# rc64kram62256ram.net
KiCad netlist of a schematic drawn in EAGLE
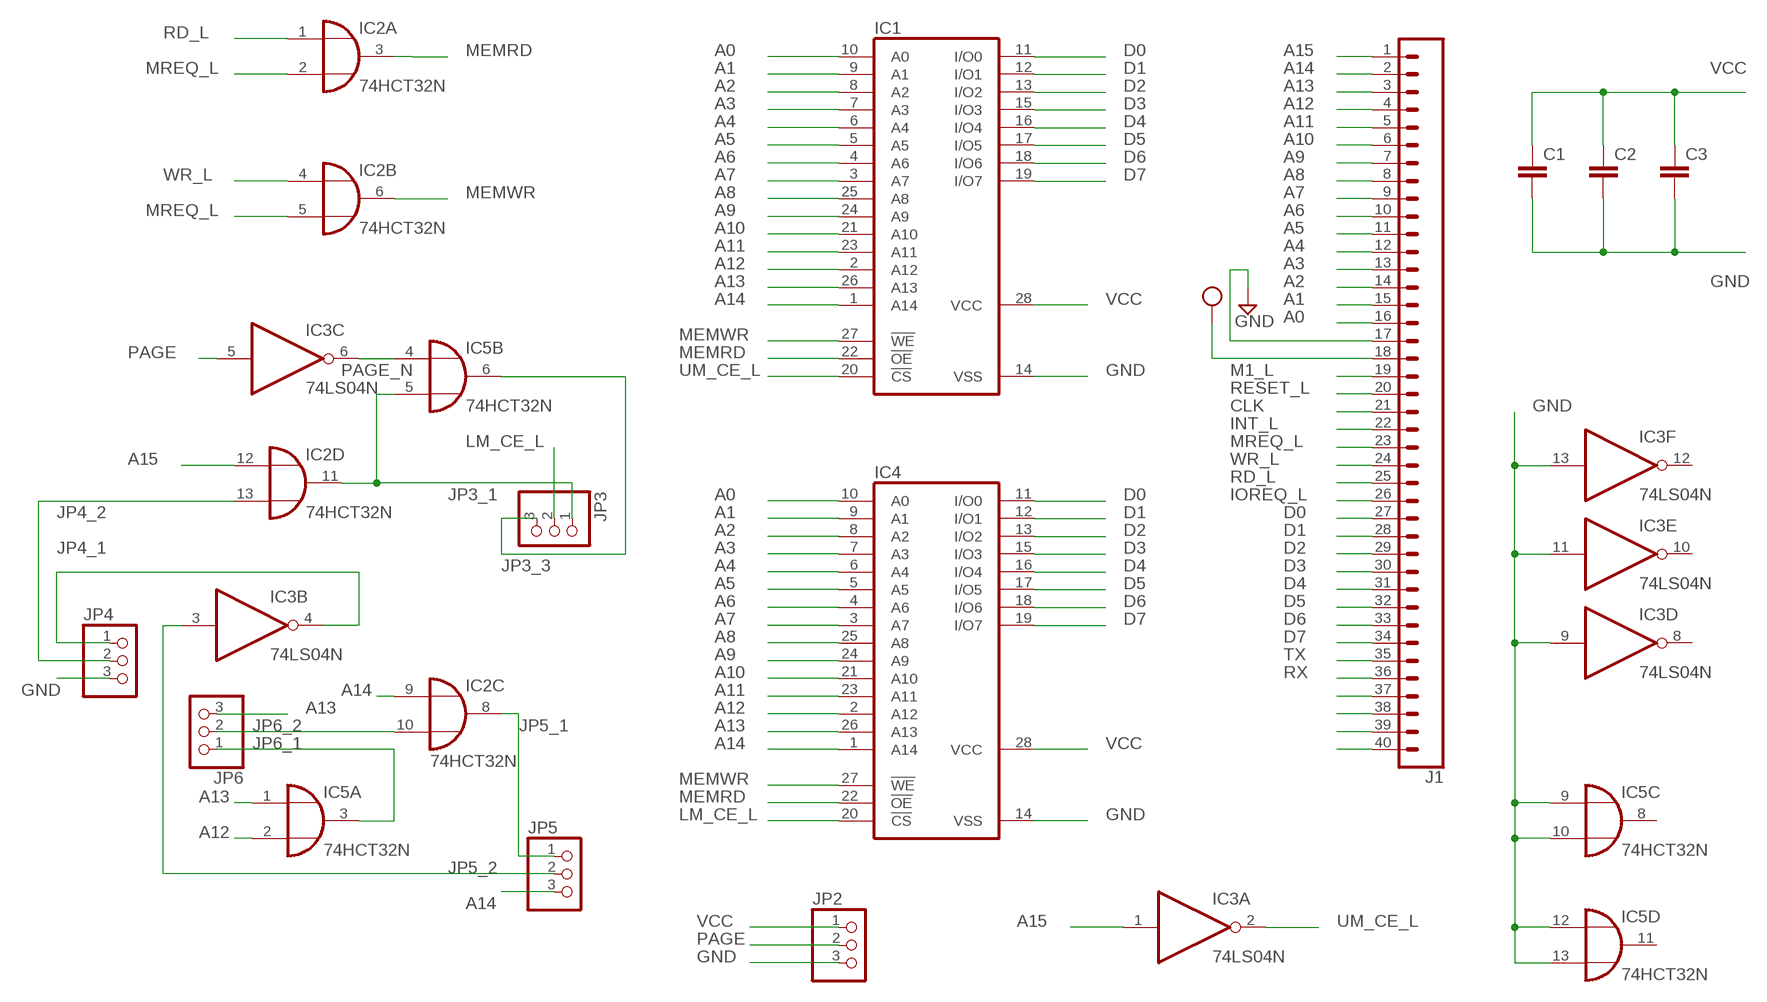
[diagram p0: schematic, sheet 1]

(export (version "E")
  (design (tool "Eeschema 10.0.6"))
  (components
    (comp (ref "C1")
      (value "C-EU050-025X075")
      (footprint "eagle-import:C050-025X075")
      (libsource (lib "eagle-import") (part "C-EU050-025X075"))
    )
    (comp (ref "C2")
      (value "C-EU050-025X075")
      (footprint "eagle-import:C050-025X075")
      (libsource (lib "eagle-import") (part "C-EU050-025X075"))
    )
    (comp (ref "C3")
      (value "C-EU050-025X075")
      (footprint "eagle-import:C050-025X075")
      (libsource (lib "eagle-import") (part "C-EU050-025X075"))
    )
    (comp (ref "IC1")
      (value "62256P")
      (footprint "eagle-import:DIL28-6")
      (libsource (lib "eagle-import") (part "62256P"))
    )
    (comp (ref "IC2")
      (value "74HCT32N")
      (footprint "eagle-import:DIL14")
      (libsource (lib "eagle-import") (part "7432NHCT"))
    )
    (comp (ref "IC3")
      (value "74LS04N")
      (footprint "eagle-import:DIL14")
      (libsource (lib "eagle-import") (part "7404NLS"))
    )
    (comp (ref "IC4")
      (value "62256P")
      (footprint "eagle-import:DIL28-6")
      (libsource (lib "eagle-import") (part "62256P"))
    )
    (comp (ref "IC5")
      (value "74HCT32N")
      (footprint "eagle-import:DIL14")
      (libsource (lib "eagle-import") (part "7432NHCT"))
    )
    (comp (ref "J1")
      (value "CONN_40OFFSET")
      (footprint "eagle-import:1X40_OFFSET")
      (libsource (lib "eagle-import") (part "CONN_40OFFSET"))
    )
    (comp (ref "JP2")
      (value "PINHD-1X3")
      (footprint "eagle-import:1X03")
      (libsource (lib "eagle-import") (part "PINHD-1X3"))
    )
    (comp (ref "JP3")
      (value "PINHD-1X3")
      (footprint "eagle-import:1X03")
      (libsource (lib "eagle-import") (part "PINHD-1X3"))
    )
    (comp (ref "JP4")
      (value "PINHD-1X3")
      (footprint "eagle-import:1X03")
      (libsource (lib "eagle-import") (part "PINHD-1X3"))
    )
    (comp (ref "JP5")
      (value "PINHD-1X3")
      (footprint "eagle-import:1X03")
      (libsource (lib "eagle-import") (part "PINHD-1X3"))
    )
    (comp (ref "JP6")
      (value "PINHD-1X3")
      (footprint "eagle-import:1X03")
      (libsource (lib "eagle-import") (part "PINHD-1X3"))
    )
  )
  (nets
    (net (code "1") (name "/A0") (class "Default")
      (node (ref "IC1") (pin "10") (pinfunction "A0_10") (pintype "input"))
      (node (ref "IC4") (pin "10") (pinfunction "A0_10") (pintype "input"))
      (node (ref "J1") (pin "16") (pinfunction "16_16") (pintype "passive"))
    )
    (net (code "2") (name "/A1") (class "Default")
      (node (ref "IC1") (pin "9") (pinfunction "A1_9") (pintype "input"))
      (node (ref "IC4") (pin "9") (pinfunction "A1_9") (pintype "input"))
      (node (ref "J1") (pin "15") (pinfunction "15_15") (pintype "passive"))
    )
    (net (code "3") (name "/A2") (class "Default")
      (node (ref "IC1") (pin "8") (pinfunction "A2_8") (pintype "input"))
      (node (ref "IC4") (pin "8") (pinfunction "A2_8") (pintype "input"))
      (node (ref "J1") (pin "14") (pinfunction "14_14") (pintype "passive"))
    )
    (net (code "4") (name "/A3") (class "Default")
      (node (ref "IC1") (pin "7") (pinfunction "A3_7") (pintype "input"))
      (node (ref "IC4") (pin "7") (pinfunction "A3_7") (pintype "input"))
      (node (ref "J1") (pin "13") (pinfunction "13_13") (pintype "passive"))
    )
    (net (code "5") (name "/A4") (class "Default")
      (node (ref "IC1") (pin "6") (pinfunction "A4_6") (pintype "input"))
      (node (ref "IC4") (pin "6") (pinfunction "A4_6") (pintype "input"))
      (node (ref "J1") (pin "12") (pinfunction "12_12") (pintype "passive"))
    )
    (net (code "6") (name "/A5") (class "Default")
      (node (ref "IC1") (pin "5") (pinfunction "A5_5") (pintype "input"))
      (node (ref "IC4") (pin "5") (pinfunction "A5_5") (pintype "input"))
      (node (ref "J1") (pin "11") (pinfunction "11_11") (pintype "passive"))
    )
    (net (code "7") (name "/A6") (class "Default")
      (node (ref "IC1") (pin "4") (pinfunction "A6_4") (pintype "input"))
      (node (ref "IC4") (pin "4") (pinfunction "A6_4") (pintype "input"))
      (node (ref "J1") (pin "10") (pinfunction "10_10") (pintype "passive"))
    )
    (net (code "8") (name "/A7") (class "Default")
      (node (ref "IC1") (pin "3") (pinfunction "A7_3") (pintype "input"))
      (node (ref "IC4") (pin "3") (pinfunction "A7_3") (pintype "input"))
      (node (ref "J1") (pin "9") (pinfunction "9_9") (pintype "passive"))
    )
    (net (code "9") (name "/A8") (class "Default")
      (node (ref "IC1") (pin "25") (pinfunction "A8_25") (pintype "input"))
      (node (ref "IC4") (pin "25") (pinfunction "A8_25") (pintype "input"))
      (node (ref "J1") (pin "8") (pinfunction "8_8") (pintype "passive"))
    )
    (net (code "10") (name "/A9") (class "Default")
      (node (ref "IC1") (pin "24") (pinfunction "A9_24") (pintype "input"))
      (node (ref "IC4") (pin "24") (pinfunction "A9_24") (pintype "input"))
      (node (ref "J1") (pin "7") (pinfunction "7_7") (pintype "passive"))
    )
    (net (code "11") (name "/A10") (class "Default")
      (node (ref "IC1") (pin "21") (pinfunction "A10_21") (pintype "input"))
      (node (ref "IC4") (pin "21") (pinfunction "A10_21") (pintype "input"))
      (node (ref "J1") (pin "6") (pinfunction "6_6") (pintype "passive"))
    )
    (net (code "12") (name "/A11") (class "Default")
      (node (ref "IC1") (pin "23") (pinfunction "A11_23") (pintype "input"))
      (node (ref "IC4") (pin "23") (pinfunction "A11_23") (pintype "input"))
      (node (ref "J1") (pin "5") (pinfunction "5_5") (pintype "passive"))
    )
    (net (code "13") (name "/A12") (class "Default")
      (node (ref "IC1") (pin "2") (pinfunction "A12_2") (pintype "input"))
      (node (ref "IC4") (pin "2") (pinfunction "A12_2") (pintype "input"))
      (node (ref "IC5") (pin "2") (pinfunction "I1_2") (pintype "input"))
      (node (ref "J1") (pin "4") (pinfunction "4_4") (pintype "passive"))
    )
    (net (code "14") (name "/A13") (class "Default")
      (node (ref "IC1") (pin "26") (pinfunction "A13_26") (pintype "input"))
      (node (ref "IC4") (pin "26") (pinfunction "A13_26") (pintype "input"))
      (node (ref "IC5") (pin "1") (pinfunction "I0_1") (pintype "input"))
      (node (ref "J1") (pin "3") (pinfunction "3_3") (pintype "passive"))
      (node (ref "JP6") (pin "3") (pinfunction "3_3") (pintype "passive"))
    )
    (net (code "15") (name "/A14") (class "Default")
      (node (ref "IC1") (pin "1") (pinfunction "A14_1") (pintype "input"))
      (node (ref "IC2") (pin "9") (pinfunction "I0_9") (pintype "input"))
      (node (ref "IC4") (pin "1") (pinfunction "A14_1") (pintype "input"))
      (node (ref "J1") (pin "2") (pinfunction "2_2") (pintype "passive"))
      (node (ref "JP5") (pin "3") (pinfunction "3_3") (pintype "passive"))
    )
    (net (code "16") (name "/A15") (class "Default")
      (node (ref "IC2") (pin "12") (pinfunction "I0_12") (pintype "input"))
      (node (ref "IC3") (pin "1") (pinfunction "I_1") (pintype "input"))
      (node (ref "J1") (pin "1") (pinfunction "1_1") (pintype "passive"))
    )
    (net (code "17") (name "/CLK") (class "Default")
      (node (ref "J1") (pin "21") (pinfunction "21_21") (pintype "passive"))
    )
    (net (code "18") (name "/D0") (class "Default")
      (node (ref "IC1") (pin "11") (pinfunction "I/O0_11") (pintype "bidirectional"))
      (node (ref "IC4") (pin "11") (pinfunction "I/O0_11") (pintype "bidirectional"))
      (node (ref "J1") (pin "27") (pinfunction "27_27") (pintype "passive"))
    )
    (net (code "19") (name "/D1") (class "Default")
      (node (ref "IC1") (pin "12") (pinfunction "I/O1_12") (pintype "bidirectional"))
      (node (ref "IC4") (pin "12") (pinfunction "I/O1_12") (pintype "bidirectional"))
      (node (ref "J1") (pin "28") (pinfunction "28_28") (pintype "passive"))
    )
    (net (code "20") (name "/D2") (class "Default")
      (node (ref "IC1") (pin "13") (pinfunction "I/O2_13") (pintype "bidirectional"))
      (node (ref "IC4") (pin "13") (pinfunction "I/O2_13") (pintype "bidirectional"))
      (node (ref "J1") (pin "29") (pinfunction "29_29") (pintype "passive"))
    )
    (net (code "21") (name "/D3") (class "Default")
      (node (ref "IC1") (pin "15") (pinfunction "I/O3_15") (pintype "bidirectional"))
      (node (ref "IC4") (pin "15") (pinfunction "I/O3_15") (pintype "bidirectional"))
      (node (ref "J1") (pin "30") (pinfunction "30_30") (pintype "passive"))
    )
    (net (code "22") (name "/D4") (class "Default")
      (node (ref "IC1") (pin "16") (pinfunction "I/O4_16") (pintype "bidirectional"))
      (node (ref "IC4") (pin "16") (pinfunction "I/O4_16") (pintype "bidirectional"))
      (node (ref "J1") (pin "31") (pinfunction "31_31") (pintype "passive"))
    )
    (net (code "23") (name "/D5") (class "Default")
      (node (ref "IC1") (pin "17") (pinfunction "I/O5_17") (pintype "bidirectional"))
      (node (ref "IC4") (pin "17") (pinfunction "I/O5_17") (pintype "bidirectional"))
      (node (ref "J1") (pin "32") (pinfunction "32_32") (pintype "passive"))
    )
    (net (code "24") (name "/D6") (class "Default")
      (node (ref "IC1") (pin "18") (pinfunction "I/O6_18") (pintype "bidirectional"))
      (node (ref "IC4") (pin "18") (pinfunction "I/O6_18") (pintype "bidirectional"))
      (node (ref "J1") (pin "33") (pinfunction "33_33") (pintype "passive"))
    )
    (net (code "25") (name "/D7") (class "Default")
      (node (ref "IC1") (pin "19") (pinfunction "I/O7_19") (pintype "bidirectional"))
      (node (ref "IC4") (pin "19") (pinfunction "I/O7_19") (pintype "bidirectional"))
      (node (ref "J1") (pin "34") (pinfunction "34_34") (pintype "passive"))
    )
    (net (code "26") (name "/INT_L") (class "Default")
      (node (ref "J1") (pin "22") (pinfunction "22_22") (pintype "passive"))
    )
    (net (code "27") (name "/IOREQ_L") (class "Default")
      (node (ref "J1") (pin "26") (pinfunction "26_26") (pintype "passive"))
    )
    (net (code "28") (name "/JP3_1") (class "Default")
      (node (ref "IC2") (pin "11") (pinfunction "O_11") (pintype "output"))
      (node (ref "IC5") (pin "5") (pinfunction "I1_5") (pintype "input"))
      (node (ref "JP3") (pin "1") (pinfunction "1_1") (pintype "passive"))
    )
    (net (code "29") (name "/JP3_3") (class "Default")
      (node (ref "IC5") (pin "6") (pinfunction "O_6") (pintype "output"))
      (node (ref "JP3") (pin "3") (pinfunction "3_3") (pintype "passive"))
    )
    (net (code "30") (name "/JP4_1") (class "Default")
      (node (ref "IC3") (pin "4") (pinfunction "O_4") (pintype "output"))
      (node (ref "JP4") (pin "1") (pinfunction "1_1") (pintype "passive"))
    )
    (net (code "31") (name "/JP4_2") (class "Default")
      (node (ref "IC2") (pin "13") (pinfunction "I1_13") (pintype "input"))
      (node (ref "JP4") (pin "2") (pinfunction "2_2") (pintype "passive"))
    )
    (net (code "32") (name "/JP5_1") (class "Default")
      (node (ref "IC2") (pin "8") (pinfunction "O_8") (pintype "output"))
      (node (ref "JP5") (pin "1") (pinfunction "1_1") (pintype "passive"))
    )
    (net (code "33") (name "/JP5_2") (class "Default")
      (node (ref "IC3") (pin "3") (pinfunction "I_3") (pintype "input"))
      (node (ref "JP5") (pin "2") (pinfunction "2_2") (pintype "passive"))
    )
    (net (code "34") (name "/JP6_1") (class "Default")
      (node (ref "IC5") (pin "3") (pinfunction "O_3") (pintype "output"))
      (node (ref "JP6") (pin "1") (pinfunction "1_1") (pintype "passive"))
    )
    (net (code "35") (name "/JP6_2") (class "Default")
      (node (ref "IC2") (pin "10") (pinfunction "I1_10") (pintype "input"))
      (node (ref "JP6") (pin "2") (pinfunction "2_2") (pintype "passive"))
    )
    (net (code "36") (name "/LM_CE_L") (class "Default")
      (node (ref "IC4") (pin "20") (pinfunction "~{CS}_20") (pintype "input"))
      (node (ref "JP3") (pin "2") (pinfunction "2_2") (pintype "passive"))
    )
    (net (code "37") (name "/M1_L") (class "Default")
      (node (ref "J1") (pin "19") (pinfunction "19_19") (pintype "passive"))
    )
    (net (code "38") (name "/MEMRD") (class "Default")
      (node (ref "IC1") (pin "22") (pinfunction "~{OE}_22") (pintype "input"))
      (node (ref "IC2") (pin "3") (pinfunction "O_3") (pintype "output"))
      (node (ref "IC4") (pin "22") (pinfunction "~{OE}_22") (pintype "input"))
    )
    (net (code "39") (name "/MEMWR") (class "Default")
      (node (ref "IC1") (pin "27") (pinfunction "~{WE}_27") (pintype "input"))
      (node (ref "IC2") (pin "6") (pinfunction "O_6") (pintype "output"))
      (node (ref "IC4") (pin "27") (pinfunction "~{WE}_27") (pintype "input"))
    )
    (net (code "40") (name "/MREQ_L") (class "Default")
      (node (ref "IC2") (pin "2") (pinfunction "I1_2") (pintype "input"))
      (node (ref "IC2") (pin "5") (pinfunction "I1_5") (pintype "input"))
      (node (ref "J1") (pin "23") (pinfunction "23_23") (pintype "passive"))
    )
    (net (code "41") (name "/PAGE") (class "Default")
      (node (ref "IC3") (pin "5") (pinfunction "I_5") (pintype "input"))
      (node (ref "JP2") (pin "2") (pinfunction "2_2") (pintype "passive"))
    )
    (net (code "42") (name "/PAGE_N") (class "Default")
      (node (ref "IC3") (pin "6") (pinfunction "O_6") (pintype "output"))
      (node (ref "IC5") (pin "4") (pinfunction "I0_4") (pintype "input"))
    )
    (net (code "43") (name "/RD_L") (class "Default")
      (node (ref "IC2") (pin "1") (pinfunction "I0_1") (pintype "input"))
      (node (ref "J1") (pin "25") (pinfunction "25_25") (pintype "passive"))
    )
    (net (code "44") (name "/RESET_L") (class "Default")
      (node (ref "J1") (pin "20") (pinfunction "20_20") (pintype "passive"))
    )
    (net (code "45") (name "/RX") (class "Default")
      (node (ref "J1") (pin "36") (pinfunction "36_36") (pintype "passive"))
    )
    (net (code "46") (name "/TX") (class "Default")
      (node (ref "J1") (pin "35") (pinfunction "35_35") (pintype "passive"))
    )
    (net (code "47") (name "/UM_CE_L") (class "Default")
      (node (ref "IC1") (pin "20") (pinfunction "~{CS}_20") (pintype "input"))
      (node (ref "IC3") (pin "2") (pinfunction "O_2") (pintype "output"))
    )
    (net (code "48") (name "/WR_L") (class "Default")
      (node (ref "IC2") (pin "4") (pinfunction "I0_4") (pintype "input"))
      (node (ref "J1") (pin "24") (pinfunction "24_24") (pintype "passive"))
    )
    (net (code "49") (name "GND") (class "Default")
      (node (ref "C1") (pin "2") (pinfunction "2_2") (pintype "passive"))
      (node (ref "C2") (pin "2") (pinfunction "2_2") (pintype "passive"))
      (node (ref "C3") (pin "2") (pinfunction "2_2") (pintype "passive"))
      (node (ref "IC1") (pin "14") (pinfunction "VSS_14") (pintype "power_in"))
      (node (ref "IC3") (pin "11") (pinfunction "I_11") (pintype "input"))
      (node (ref "IC3") (pin "13") (pinfunction "I_13") (pintype "input"))
      (node (ref "IC3") (pin "9") (pinfunction "I_9") (pintype "input"))
      (node (ref "IC4") (pin "14") (pinfunction "VSS_14") (pintype "power_in"))
      (node (ref "IC5") (pin "10") (pinfunction "I1_10") (pintype "input"))
      (node (ref "IC5") (pin "12") (pinfunction "I0_12") (pintype "input"))
      (node (ref "IC5") (pin "13") (pinfunction "I1_13") (pintype "input"))
      (node (ref "IC5") (pin "9") (pinfunction "I0_9") (pintype "input"))
      (node (ref "J1") (pin "17") (pinfunction "17_17") (pintype "passive"))
      (node (ref "JP2") (pin "3") (pinfunction "3_3") (pintype "passive"))
      (node (ref "JP4") (pin "3") (pinfunction "3_3") (pintype "passive"))
    )
    (net (code "50") (name "VCC") (class "Default")
      (node (ref "C1") (pin "1") (pinfunction "1_1") (pintype "passive"))
      (node (ref "C2") (pin "1") (pinfunction "1_1") (pintype "passive"))
      (node (ref "C3") (pin "1") (pinfunction "1_1") (pintype "passive"))
      (node (ref "IC1") (pin "28") (pinfunction "VCC_28") (pintype "power_in"))
      (node (ref "IC4") (pin "28") (pinfunction "VCC_28") (pintype "power_in"))
      (node (ref "J1") (pin "18") (pinfunction "18_18") (pintype "passive"))
      (node (ref "JP2") (pin "1") (pinfunction "1_1") (pintype "passive"))
    )
    (net (code "51") (name "unconnected-(IC3D-O-Pad8)") (class "Default")
      (node (ref "IC3") (pin "8") (pinfunction "O_8") (pintype "output"))
    )
    (net (code "52") (name "unconnected-(IC3E-O-Pad10)") (class "Default")
      (node (ref "IC3") (pin "10") (pinfunction "O_10") (pintype "output"))
    )
    (net (code "53") (name "unconnected-(IC3F-O-Pad12)") (class "Default")
      (node (ref "IC3") (pin "12") (pinfunction "O_12") (pintype "output"))
    )
    (net (code "54") (name "unconnected-(IC5C-O-Pad8)") (class "Default")
      (node (ref "IC5") (pin "8") (pinfunction "O_8") (pintype "output"))
    )
    (net (code "55") (name "unconnected-(IC5D-O-Pad11)") (class "Default")
      (node (ref "IC5") (pin "11") (pinfunction "O_11") (pintype "output"))
    )
    (net (code "56") (name "unconnected-(J1-Pad37)") (class "Default")
      (node (ref "J1") (pin "37") (pinfunction "37_37") (pintype "passive"))
    )
    (net (code "57") (name "unconnected-(J1-Pad38)") (class "Default")
      (node (ref "J1") (pin "38") (pinfunction "38_38") (pintype "passive"))
    )
    (net (code "58") (name "unconnected-(J1-Pad39)") (class "Default")
      (node (ref "J1") (pin "39") (pinfunction "39_39") (pintype "passive"))
    )
    (net (code "59") (name "unconnected-(J1-Pad40)") (class "Default")
      (node (ref "J1") (pin "40") (pinfunction "40_40") (pintype "passive"))
    )
  )
)
